# power_regulator.net
KiCad netlist of a schematic drawn in Altium Designer
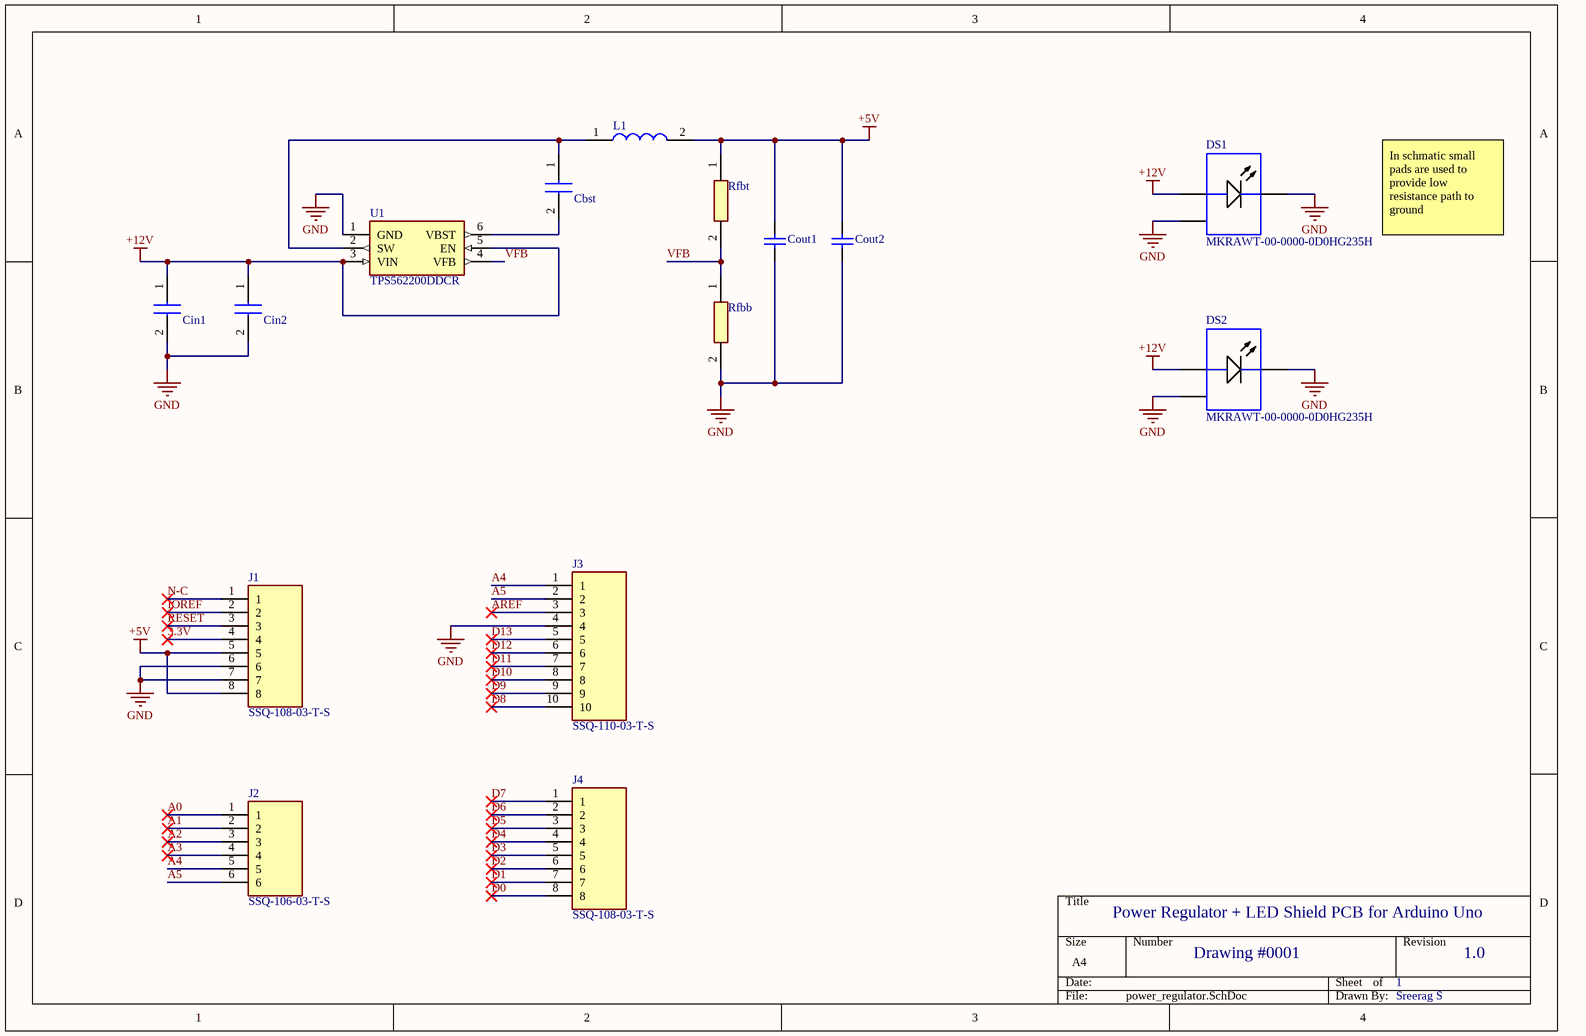
[diagram p0: power_regulator.SchDoc]

(export (version "E")
  (design (tool "Eeschema 10.0.6"))
  (components
    (comp (ref "Cbst")
      (value "08053C104KAT2A")
      (footprint "SamacSys:CAPC2012X94N")
      (description "Capacitor")
      (fields (field (name "MOUSER PART NUMBER") "581-08053C104K"))
      (libsource (lib "*") (part "08053C104KAT2A"))
    )
    (comp (ref "Cin1")
      (value "C2012X5R1V106K085AC")
      (footprint "SamacSys:C2012_Commercial")
      (description "Capacitor")
      (fields (field (name "MOUSER PART NUMBER") "810-C2012X5R1V106K0C"))
      (libsource (lib "*") (part "C2012X5R1V106K085AC"))
    )
    (comp (ref "Cin2")
      (value "C2012X5R1V106K085AC")
      (footprint "SamacSys:C2012_Commercial")
      (description "Capacitor")
      (fields (field (name "MOUSER PART NUMBER") "810-C2012X5R1V106K0C"))
      (libsource (lib "*") (part "C2012X5R1V106K085AC"))
    )
    (comp (ref "Cout1")
      (value "C1608X5R1A226M080AC")
      (footprint "CAPC1608X100X20ML10")
      (description "Chip Capacitor, 22 uF, +/- 20%, 10 V, -55 to 85 degC, 0603 (1608 Metric), RoHS, Tape and Reel")
      (fields (field (name "MANUFACTURER") "TDK") (field (name "TOLERANCE") "±20%"))
      (libsource (lib "Altium Content Vault") (part "CAP-NP-2"))
    )
    (comp (ref "Cout2")
      (value "C1608X5R1A226M080AC")
      (footprint "CAPC1608X100X20ML10")
      (description "Chip Capacitor, 22 uF, +/- 20%, 10 V, -55 to 85 degC, 0603 (1608 Metric), RoHS, Tape and Reel")
      (fields (field (name "MANUFACTURER") "TDK") (field (name "TOLERANCE") "±20%"))
      (libsource (lib "Altium Content Vault") (part "CAP-NP-2"))
    )
    (comp (ref "DS1")
      (value "MKRAWT-00-0000-0D0HG235H")
      (footprint "CREE-MK-R-2_V")
      (description "LED, White, 12 V, 2-Pin SMD, RoHS, Tape and Reel")
      (libsource (lib "Altium Content Vault") (part "LED_WHITE-3"))
    )
    (comp (ref "DS2")
      (value "MKRAWT-00-0000-0D0HG235H")
      (footprint "CREE-MK-R-2_V")
      (description "LED, White, 12 V, 2-Pin SMD, RoHS, Tape and Reel")
      (libsource (lib "Altium Content Vault") (part "LED_WHITE-3"))
    )
    (comp (ref "J1")
      (value "SSQ-108-03-T-S")
      (footprint "SamacSys:RHDR8W64P254_1X8_2083X241X851P")
      (description "Connector")
      (fields (field (name "MOUSER PART NUMBER") "200-SSQ10803TS"))
      (libsource (lib "*") (part "SSQ-108-03-T-S"))
    )
    (comp (ref "J2")
      (value "SSQ-106-03-T-S")
      (footprint "SamacSys:RHDR6W64P254_1X6_1575X241X851P")
      (description "Connector")
      (fields (field (name "MOUSER PART NUMBER") "200-SSQ10603TS"))
      (libsource (lib "*") (part "SSQ-106-03-T-S"))
    )
    (comp (ref "J3")
      (value "SSQ-110-03-T-S")
      (footprint "SamacSys:RHDR10W64P254_1X10_2591X241X851P")
      (description "Connector")
      (fields (field (name "MOUSER PART NUMBER") "200-SSQ11003TS"))
      (libsource (lib "*") (part "SSQ-110-03-T-S"))
    )
    (comp (ref "J4")
      (value "SSQ-108-03-T-S")
      (footprint "SamacSys:RHDR8W64P254_1X8_2083X241X851P")
      (description "Connector")
      (fields (field (name "MOUSER PART NUMBER") "200-SSQ10803TS"))
      (libsource (lib "*") (part "SSQ-108-03-T-S"))
    )
    (comp (ref "L1")
      (value "SRN6045-4R7Y")
      (footprint "SamacSys:SRN6045_1")
      (description "Inductor")
      (fields (field (name "MOUSER PART NUMBER") "652-SRN6045-4R7Y"))
      (libsource (lib "*") (part "SRN6045-4R7Y"))
    )
    (comp (ref "Rfbb")
      (value "RC0201FR-0710KL")
      (footprint "SamacSys:RESC0603X26N")
      (description "Resistor")
      (fields (field (name "MOUSER PART NUMBER") "603-RC0201FR-0710KL"))
      (libsource (lib "*") (part "RC0201FR-0710KL"))
    )
    (comp (ref "Rfbt")
      (value "RC0201FR-0756K2L")
      (footprint "SamacSys:RESC0603X26N")
      (description "Resistor")
      (fields (field (name "MOUSER PART NUMBER") "603-RC0201FR-0756K2L"))
      (libsource (lib "*") (part "RC0201FR-0756K2L"))
    )
    (comp (ref "U1")
      (value "TPS562200DDCR")
      (footprint "SamacSys:SOT95P280X110-6N")
      (description "Undefined or Miscellaneous")
      (fields (field (name "MOUSER PART NUMBER") "595-TPS562200DDCR"))
      (libsource (lib "*") (part "TPS562200DDCR"))
    )
  )
  (nets
    (net (code "1") (name "+5V") (class "Default")
      (node (ref "Cout1") (pin "2") (pinfunction "2_2") (pintype "passive"))
      (node (ref "Cout2") (pin "2") (pinfunction "2_2") (pintype "passive"))
      (node (ref "J1") (pin "5") (pinfunction "5_5") (pintype "passive"))
      (node (ref "J1") (pin "8") (pinfunction "8_8") (pintype "passive"))
      (node (ref "L1") (pin "2") (pinfunction "2_2") (pintype "passive"))
      (node (ref "Rfbt") (pin "1") (pinfunction "1_1") (pintype "passive"))
    )
    (net (code "2") (name "+12V") (class "Default")
      (node (ref "Cin1") (pin "1") (pinfunction "1_1") (pintype "passive"))
      (node (ref "Cin2") (pin "1") (pinfunction "1_1") (pintype "passive"))
      (node (ref "DS1") (pin "1") (pinfunction "A_1") (pintype "passive"))
      (node (ref "DS2") (pin "1") (pinfunction "A_1") (pintype "passive"))
      (node (ref "U1") (pin "3") (pinfunction "VIN_3") (pintype "input"))
      (node (ref "U1") (pin "5") (pinfunction "EN_5") (pintype "input"))
    )
    (net (code "3") (name "/3.3V") (class "Default")
      (node (ref "J1") (pin "4") (pinfunction "4_4") (pintype "passive+no_connect"))
    )
    (net (code "4") (name "/A0") (class "Default")
      (node (ref "J2") (pin "1") (pinfunction "1_1") (pintype "passive+no_connect"))
    )
    (net (code "5") (name "/A1") (class "Default")
      (node (ref "J2") (pin "2") (pinfunction "2_2") (pintype "passive+no_connect"))
    )
    (net (code "6") (name "/A2") (class "Default")
      (node (ref "J2") (pin "3") (pinfunction "3_3") (pintype "passive+no_connect"))
    )
    (net (code "7") (name "/A3") (class "Default")
      (node (ref "J2") (pin "4") (pinfunction "4_4") (pintype "passive+no_connect"))
    )
    (net (code "8") (name "/A4") (class "Default")
      (node (ref "J2") (pin "5") (pinfunction "5_5") (pintype "passive"))
      (node (ref "J3") (pin "1") (pinfunction "1_1") (pintype "passive"))
    )
    (net (code "9") (name "/A5") (class "Default")
      (node (ref "J2") (pin "6") (pinfunction "6_6") (pintype "passive"))
      (node (ref "J3") (pin "2") (pinfunction "2_2") (pintype "passive"))
    )
    (net (code "10") (name "/AREF") (class "Default")
      (node (ref "J3") (pin "3") (pinfunction "3_3") (pintype "passive+no_connect"))
    )
    (net (code "11") (name "/D0") (class "Default")
      (node (ref "J4") (pin "8") (pinfunction "8_8") (pintype "passive+no_connect"))
    )
    (net (code "12") (name "/D1") (class "Default")
      (node (ref "J4") (pin "7") (pinfunction "7_7") (pintype "passive+no_connect"))
    )
    (net (code "13") (name "/D2") (class "Default")
      (node (ref "J4") (pin "6") (pinfunction "6_6") (pintype "passive+no_connect"))
    )
    (net (code "14") (name "/D3") (class "Default")
      (node (ref "J4") (pin "5") (pinfunction "5_5") (pintype "passive+no_connect"))
    )
    (net (code "15") (name "/D4") (class "Default")
      (node (ref "J4") (pin "4") (pinfunction "4_4") (pintype "passive+no_connect"))
    )
    (net (code "16") (name "/D5") (class "Default")
      (node (ref "J4") (pin "3") (pinfunction "3_3") (pintype "passive+no_connect"))
    )
    (net (code "17") (name "/D6") (class "Default")
      (node (ref "J4") (pin "2") (pinfunction "2_2") (pintype "passive+no_connect"))
    )
    (net (code "18") (name "/D7") (class "Default")
      (node (ref "J4") (pin "1") (pinfunction "1_1") (pintype "passive+no_connect"))
    )
    (net (code "19") (name "/D8") (class "Default")
      (node (ref "J3") (pin "10") (pinfunction "10_10") (pintype "passive+no_connect"))
    )
    (net (code "20") (name "/D9") (class "Default")
      (node (ref "J3") (pin "9") (pinfunction "9_9") (pintype "passive+no_connect"))
    )
    (net (code "21") (name "/D10") (class "Default")
      (node (ref "J3") (pin "8") (pinfunction "8_8") (pintype "passive+no_connect"))
    )
    (net (code "22") (name "/D11") (class "Default")
      (node (ref "J3") (pin "7") (pinfunction "7_7") (pintype "passive+no_connect"))
    )
    (net (code "23") (name "/D12") (class "Default")
      (node (ref "J3") (pin "6") (pinfunction "6_6") (pintype "passive+no_connect"))
    )
    (net (code "24") (name "/D13") (class "Default")
      (node (ref "J3") (pin "5") (pinfunction "5_5") (pintype "passive+no_connect"))
    )
    (net (code "25") (name "/IOREF") (class "Default")
      (node (ref "J1") (pin "2") (pinfunction "2_2") (pintype "passive+no_connect"))
    )
    (net (code "26") (name "/N-C") (class "Default")
      (node (ref "J1") (pin "1") (pinfunction "1_1") (pintype "passive+no_connect"))
    )
    (net (code "27") (name "/RESET") (class "Default")
      (node (ref "J1") (pin "3") (pinfunction "3_3") (pintype "passive+no_connect"))
    )
    (net (code "28") (name "/VFB") (class "Default")
      (node (ref "Rfbb") (pin "1") (pinfunction "1_1") (pintype "passive"))
      (node (ref "Rfbt") (pin "2") (pinfunction "2_2") (pintype "passive"))
      (node (ref "U1") (pin "4") (pinfunction "VFB_4") (pintype "output"))
    )
    (net (code "29") (name "GND") (class "Default")
      (node (ref "Cin1") (pin "2") (pinfunction "2_2") (pintype "passive"))
      (node (ref "Cin2") (pin "2") (pinfunction "2_2") (pintype "passive"))
      (node (ref "Cout1") (pin "1") (pinfunction "1_1") (pintype "passive"))
      (node (ref "Cout2") (pin "1") (pinfunction "1_1") (pintype "passive"))
      (node (ref "DS1") (pin "2") (pinfunction "K_2") (pintype "passive"))
      (node (ref "DS1") (pin "3") (pinfunction "EP_3") (pintype "passive"))
      (node (ref "DS2") (pin "2") (pinfunction "K_2") (pintype "passive"))
      (node (ref "DS2") (pin "3") (pinfunction "EP_3") (pintype "passive"))
      (node (ref "J1") (pin "6") (pinfunction "6_6") (pintype "passive"))
      (node (ref "J1") (pin "7") (pinfunction "7_7") (pintype "passive"))
      (node (ref "J3") (pin "4") (pinfunction "4_4") (pintype "passive"))
      (node (ref "Rfbb") (pin "2") (pinfunction "2_2") (pintype "passive"))
      (node (ref "U1") (pin "1") (pinfunction "GND_1") (pintype "power_in"))
    )
    (net (code "30") (name "Net-(U1-SW)") (class "Default")
      (node (ref "Cbst") (pin "1") (pinfunction "1_1") (pintype "passive"))
      (node (ref "L1") (pin "1") (pinfunction "1_1") (pintype "passive"))
      (node (ref "U1") (pin "2") (pinfunction "SW_2") (pintype "output"))
    )
    (net (code "31") (name "Net-(U1-VBST)") (class "Default")
      (node (ref "Cbst") (pin "2") (pinfunction "2_2") (pintype "passive"))
      (node (ref "U1") (pin "6") (pinfunction "VBST_6") (pintype "output"))
    )
  )
)
